# UTOS_V1_0.net
KiCad netlist of a schematic drawn in Altium Designer
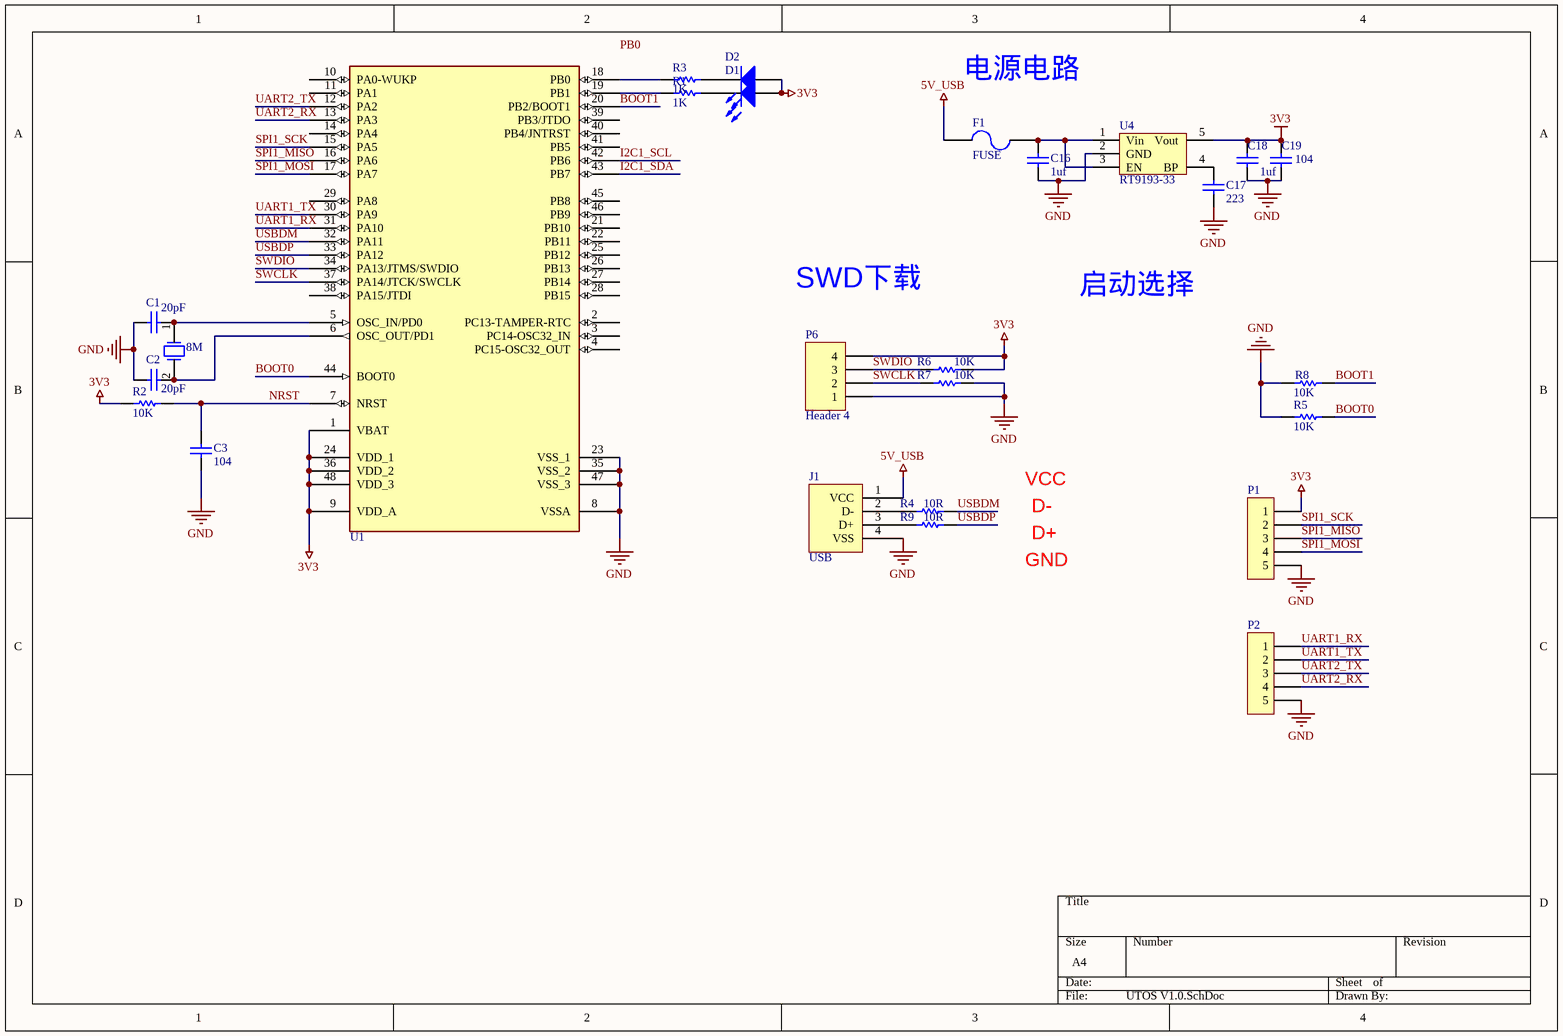
[diagram p0: UTOS V1.0.SchDoc]

(export (version "E")
  (design (tool "Eeschema 10.0.6"))
  (components
    (comp (ref "8M") (value "XTAL") (footprint "xtal") (libsource (lib "MYLIB") (part "XTAL")))
    (comp (ref "C1")
      (value "20pF")
      (footprint "C-RAD-0603")
      (description "Capacitor")
      (fields (field (name "Comment") "C0603") (field (name "PUBLISHER") "Altium Limited"))
      (libsource (lib "MYLIB") (part "C-RAD-0603"))
    )
    (comp (ref "C2")
      (value "20pF")
      (footprint "C-RAD-0603")
      (description "Capacitor")
      (fields (field (name "Comment") "C0603") (field (name "PUBLISHER") "Altium Limited"))
      (libsource (lib "MYLIB") (part "C-RAD-0603"))
    )
    (comp (ref "C3")
      (value "104")
      (footprint "C-RAD-0603")
      (description "Capacitor")
      (fields (field (name "Comment") "C0603") (field (name "PUBLISHER") "Altium Limited"))
      (libsource (lib "MYLIB") (part "C-RAD-0603"))
    )
    (comp (ref "C16")
      (value "1uf")
      (footprint "C-RAD-0603")
      (description "Capacitor")
      (libsource (lib "Cheetie Integrated Library 2017") (part "CAP"))
    )
    (comp (ref "C17")
      (value "223")
      (footprint "C-RAD-0603")
      (description "Capacitor")
      (libsource (lib "Cheetie Integrated Library 2017") (part "CAP"))
    )
    (comp (ref "C18")
      (value "1uf")
      (footprint "C-RAD-0603")
      (description "Capacitor")
      (libsource (lib "Cheetie Integrated Library 2017") (part "CAP"))
    )
    (comp (ref "C19")
      (value "104")
      (footprint "C-RAD-0603")
      (description "Capacitor")
      (libsource (lib "Cheetie Integrated Library 2017") (part "CAP"))
    )
    (comp (ref "D1")
      (value "D0603")
      (footprint "0603-1")
      (description "Typical RED, GREEN, YELLOW, AMBER GaAs LED")
      (fields (field (name "PUBLISHER") "Altium Limited"))
      (libsource (lib "MYLIB") (part "D0603"))
    )
    (comp (ref "D2")
      (value "D0603")
      (footprint "0603-1")
      (description "Typical RED, GREEN, YELLOW, AMBER GaAs LED")
      (fields (field (name "PUBLISHER") "Altium Limited"))
      (libsource (lib "MYLIB") (part "D0603"))
    )
    (comp (ref "F1") (value "FUSE") (footprint "0603-1") (libsource (lib "MYLIB") (part "FUSE")))
    (comp (ref "J1")
      (value "USB")
      (footprint "USB")
      (description "USB接口")
      (libsource (lib "Cheetie Integrated Library 2017") (part "USB"))
    )
    (comp (ref "P1")
      (value "~")
      (footprint "p5")
      (libsource (lib "Cheetie Integrated Library 2017") (part "p5"))
    )
    (comp (ref "P2")
      (value "~")
      (footprint "p5")
      (libsource (lib "Cheetie Integrated Library 2017") (part "p5"))
    )
    (comp (ref "P6")
      (value "Header 4")
      (footprint "p4")
      (description "Header, 4-Pin")
      (fields (field (name "PUBLISHER") "Altium Limited"))
      (libsource (lib "Miscellaneous Connectors") (part "Header 4"))
    )
    (comp (ref "R1")
      (value "1K")
      (footprint "0603-1")
      (description "Resistor")
      (fields (field (name "Comment") "R0603") (field (name "PUBLISHER") "Altium Limited"))
      (libsource (lib "MYLIB") (part "0603-1"))
    )
    (comp (ref "R2")
      (value "10K")
      (footprint "r0603")
      (description "Resistor")
      (fields (field (name "Comment") "R0603") (field (name "PUBLISHER") "Altium Limited"))
      (libsource (lib "MYLIB") (part "0603-1"))
    )
    (comp (ref "R3")
      (value "1K")
      (footprint "0603-1")
      (description "Resistor")
      (fields (field (name "Comment") "R0603") (field (name "PUBLISHER") "Altium Limited"))
      (libsource (lib "MYLIB") (part "0603-1"))
    )
    (comp (ref "R4")
      (value "10R")
      (footprint "0603-1")
      (description "Resistor")
      (fields (field (name "Comment") "R0805") (field (name "PUBLISHER") "Altium Limited"))
      (libsource (lib "component_lib") (part "R0805"))
    )
    (comp (ref "R5")
      (value "10K")
      (footprint "0603-1")
      (description "Resistor")
      (fields (field (name "Comment") "R0603") (field (name "PUBLISHER") "Altium Limited"))
      (libsource (lib "MYLIB") (part "0603-1"))
    )
    (comp (ref "R6")
      (value "10K")
      (footprint "0603-1")
      (description "Resistor")
      (fields (field (name "Comment") "R0805") (field (name "PUBLISHER") "Altium Limited"))
      (libsource (lib "component_lib") (part "R0805"))
    )
    (comp (ref "R7")
      (value "10K")
      (footprint "0603-1")
      (description "Resistor")
      (fields (field (name "Comment") "R0805") (field (name "PUBLISHER") "Altium Limited"))
      (libsource (lib "component_lib") (part "R0805"))
    )
    (comp (ref "R8")
      (value "10K")
      (footprint "0603-1")
      (description "Resistor")
      (fields (field (name "Comment") "R0603") (field (name "PUBLISHER") "Altium Limited"))
      (libsource (lib "MYLIB") (part "R0603"))
    )
    (comp (ref "R9")
      (value "10R")
      (footprint "0603-1")
      (description "Resistor")
      (fields (field (name "Comment") "R0805") (field (name "PUBLISHER") "Altium Limited"))
      (libsource (lib "component_lib") (part "R0805"))
    )
    (comp (ref "U1")
      (value "STM32F103C8T6")
      (footprint "LQFP48")
      (description "LowPower MCU")
      (libsource (lib "MYLIB") (part "STM32F103C8T6"))
    )
    (comp (ref "U4")
      (value "RT9193-33")
      (footprint "SOT23-5")
      (libsource (lib "Cheetie Integrated Library 2017") (part "RT9193-33"))
    )
  )
  (nets
    (net (code "1") (name "/BOOT0") (class "Default")
      (node (ref "R5") (pin "1") (pinfunction "1_1") (pintype "passive"))
      (node (ref "U1") (pin "44") (pinfunction "BOOT0_44") (pintype "input"))
    )
    (net (code "2") (name "/BOOT1") (class "Default")
      (node (ref "R8") (pin "2") (pinfunction "2_2") (pintype "passive"))
      (node (ref "U1") (pin "20") (pinfunction "PB2/BOOT1_20") (pintype "bidirectional"))
    )
    (net (code "3") (name "/I2C1_SCL") (class "Default")
      (node (ref "U1") (pin "42") (pinfunction "PB6_42") (pintype "bidirectional"))
    )
    (net (code "4") (name "/I2C1_SDA") (class "Default")
      (node (ref "U1") (pin "43") (pinfunction "PB7_43") (pintype "bidirectional"))
    )
    (net (code "5") (name "/NRST") (class "Default")
      (node (ref "C3") (pin "2") (pinfunction "2_2") (pintype "passive"))
      (node (ref "R2") (pin "1") (pinfunction "1_1") (pintype "passive"))
      (node (ref "U1") (pin "7") (pinfunction "NRST_7") (pintype "bidirectional"))
    )
    (net (code "7") (name "/SPI1_MISO") (class "Default")
      (node (ref "P1") (pin "3") (pinfunction "3_3") (pintype "passive"))
      (node (ref "U1") (pin "16") (pinfunction "PA6_16") (pintype "bidirectional"))
    )
    (net (code "8") (name "/SPI1_MOSI") (class "Default")
      (node (ref "P1") (pin "4") (pinfunction "4_4") (pintype "passive"))
      (node (ref "U1") (pin "17") (pinfunction "PA7_17") (pintype "bidirectional"))
    )
    (net (code "9") (name "/SPI1_SCK") (class "Default")
      (node (ref "P1") (pin "2") (pinfunction "2_2") (pintype "passive"))
      (node (ref "U1") (pin "15") (pinfunction "PA5_15") (pintype "bidirectional"))
    )
    (net (code "10") (name "/SWCLK") (class "Default")
      (node (ref "P6") (pin "2") (pinfunction "2_2") (pintype "passive"))
      (node (ref "R7") (pin "2") (pinfunction "2_2") (pintype "passive"))
      (node (ref "U1") (pin "37") (pinfunction "PA14/JTCK/SWCLK_37") (pintype "bidirectional"))
    )
    (net (code "11") (name "/SWDIO") (class "Default")
      (node (ref "P6") (pin "3") (pinfunction "3_3") (pintype "passive"))
      (node (ref "R6") (pin "2") (pinfunction "2_2") (pintype "passive"))
      (node (ref "U1") (pin "34") (pinfunction "PA13/JTMS/SWDIO_34") (pintype "bidirectional"))
    )
    (net (code "12") (name "/UART1_RX") (class "Default")
      (node (ref "P2") (pin "1") (pinfunction "1_1") (pintype "passive"))
      (node (ref "U1") (pin "31") (pinfunction "PA10_31") (pintype "bidirectional"))
    )
    (net (code "13") (name "/UART1_TX") (class "Default")
      (node (ref "P2") (pin "2") (pinfunction "2_2") (pintype "passive"))
      (node (ref "U1") (pin "30") (pinfunction "PA9_30") (pintype "bidirectional"))
    )
    (net (code "14") (name "/UART2_RX") (class "Default")
      (node (ref "P2") (pin "4") (pinfunction "4_4") (pintype "passive"))
      (node (ref "U1") (pin "13") (pinfunction "PA3_13") (pintype "bidirectional"))
    )
    (net (code "15") (name "/UART2_TX") (class "Default")
      (node (ref "P2") (pin "3") (pinfunction "3_3") (pintype "passive"))
      (node (ref "U1") (pin "12") (pinfunction "PA2_12") (pintype "bidirectional"))
    )
    (net (code "16") (name "/USBDM") (class "Default")
      (node (ref "R4") (pin "1") (pinfunction "1_1") (pintype "passive"))
      (node (ref "U1") (pin "32") (pinfunction "PA11_32") (pintype "bidirectional"))
    )
    (net (code "17") (name "/USBDP") (class "Default")
      (node (ref "R9") (pin "1") (pinfunction "1_1") (pintype "passive"))
      (node (ref "U1") (pin "33") (pinfunction "PA12_33") (pintype "bidirectional"))
    )
    (net (code "18") (name "3V3") (class "Default")
      (node (ref "C18") (pin "2") (pinfunction "2_2") (pintype "passive"))
      (node (ref "C19") (pin "2") (pinfunction "2_2") (pintype "passive"))
      (node (ref "D1") (pin "1") (pinfunction "A_1") (pintype "passive"))
      (node (ref "D2") (pin "1") (pinfunction "A_1") (pintype "passive"))
      (node (ref "P1") (pin "1") (pinfunction "1_1") (pintype "passive"))
      (node (ref "P6") (pin "4") (pinfunction "4_4") (pintype "passive"))
      (node (ref "R2") (pin "2") (pinfunction "2_2") (pintype "passive"))
      (node (ref "R6") (pin "1") (pinfunction "1_1") (pintype "passive"))
      (node (ref "U1") (pin "1") (pinfunction "VBAT_1") (pintype "passive"))
      (node (ref "U1") (pin "24") (pinfunction "VDD_1_24") (pintype "passive"))
      (node (ref "U1") (pin "36") (pinfunction "VDD_2_36") (pintype "passive"))
      (node (ref "U1") (pin "48") (pinfunction "VDD_3_48") (pintype "passive"))
      (node (ref "U1") (pin "9") (pinfunction "VDD_A_9") (pintype "passive"))
      (node (ref "U4") (pin "5") (pinfunction "Vout_5") (pintype "passive"))
    )
    (net (code "19") (name "5V_USB") (class "Default")
      (node (ref "F1") (pin "2") (pinfunction "2_2") (pintype "passive"))
      (node (ref "J1") (pin "1") (pinfunction "VCC_1") (pintype "passive"))
    )
    (net (code "20") (name "GND") (class "Default")
      (node (ref "C1") (pin "2") (pinfunction "2_2") (pintype "passive"))
      (node (ref "C16") (pin "1") (pinfunction "1_1") (pintype "passive"))
      (node (ref "C17") (pin "1") (pinfunction "1_1") (pintype "passive"))
      (node (ref "C18") (pin "1") (pinfunction "1_1") (pintype "passive"))
      (node (ref "C19") (pin "1") (pinfunction "1_1") (pintype "passive"))
      (node (ref "C2") (pin "2") (pinfunction "2_2") (pintype "passive"))
      (node (ref "C3") (pin "1") (pinfunction "1_1") (pintype "passive"))
      (node (ref "J1") (pin "4") (pinfunction "VSS_4") (pintype "passive"))
      (node (ref "P1") (pin "5") (pinfunction "5_5") (pintype "passive"))
      (node (ref "P2") (pin "5") (pinfunction "5_5") (pintype "passive"))
      (node (ref "P6") (pin "1") (pinfunction "1_1") (pintype "passive"))
      (node (ref "R5") (pin "2") (pinfunction "2_2") (pintype "passive"))
      (node (ref "R7") (pin "1") (pinfunction "1_1") (pintype "passive"))
      (node (ref "R8") (pin "1") (pinfunction "1_1") (pintype "passive"))
      (node (ref "U1") (pin "23") (pinfunction "VSS_1_23") (pintype "passive"))
      (node (ref "U1") (pin "35") (pinfunction "VSS_2_35") (pintype "passive"))
      (node (ref "U1") (pin "47") (pinfunction "VSS_3_47") (pintype "passive"))
      (node (ref "U1") (pin "8") (pinfunction "VSSA_8") (pintype "passive"))
      (node (ref "U4") (pin "2") (pinfunction "GND_2") (pintype "passive"))
    )
    (net (code "21") (name "Net-(D1-K)") (class "Default")
      (node (ref "D1") (pin "2") (pinfunction "K_2") (pintype "passive"))
      (node (ref "R1") (pin "2") (pinfunction "2_2") (pintype "passive"))
    )
    (net (code "22") (name "Net-(D2-K)") (class "Default")
      (node (ref "D2") (pin "2") (pinfunction "K_2") (pintype "passive"))
      (node (ref "R3") (pin "2") (pinfunction "2_2") (pintype "passive"))
    )
    (net (code "23") (name "Net-(J1-D+)") (class "Default")
      (node (ref "J1") (pin "3") (pinfunction "D+_3") (pintype "passive"))
      (node (ref "R9") (pin "2") (pinfunction "2_2") (pintype "passive"))
    )
    (net (code "24") (name "Net-(J1-D-)") (class "Default")
      (node (ref "J1") (pin "2") (pinfunction "D-_2") (pintype "passive"))
      (node (ref "R4") (pin "2") (pinfunction "2_2") (pintype "passive"))
    )
    (net (code "25") (name "Net-(U1-OSC_IN{slash}PD0)") (class "Default")
      (node (ref "8M") (pin "1") (pinfunction "1_1") (pintype "passive"))
      (node (ref "C1") (pin "1") (pinfunction "1_1") (pintype "passive"))
      (node (ref "U1") (pin "5") (pinfunction "OSC_IN/PD0_5") (pintype "input"))
    )
    (net (code "26") (name "Net-(U1-OSC_OUT{slash}PD1)") (class "Default")
      (node (ref "8M") (pin "2") (pinfunction "2_2") (pintype "passive"))
      (node (ref "C2") (pin "1") (pinfunction "1_1") (pintype "passive"))
      (node (ref "U1") (pin "6") (pinfunction "OSC_OUT/PD1_6") (pintype "output"))
    )
    (net (code "27") (name "Net-(U1-PB0)") (class "Default")
      (node (ref "R3") (pin "1") (pinfunction "1_1") (pintype "passive"))
      (node (ref "U1") (pin "18") (pinfunction "PB0_18") (pintype "bidirectional"))
    )
    (net (code "28") (name "Net-(U1-PB1)") (class "Default")
      (node (ref "R1") (pin "1") (pinfunction "1_1") (pintype "passive"))
      (node (ref "U1") (pin "19") (pinfunction "PB1_19") (pintype "bidirectional"))
    )
    (net (code "29") (name "Net-(U4-BP)") (class "Default")
      (node (ref "C17") (pin "2") (pinfunction "2_2") (pintype "passive"))
      (node (ref "U4") (pin "4") (pinfunction "BP_4") (pintype "passive"))
    )
    (net (code "30") (name "Net-(U4-EN)") (class "Default")
      (node (ref "C16") (pin "2") (pinfunction "2_2") (pintype "passive"))
      (node (ref "F1") (pin "1") (pinfunction "1_1") (pintype "passive"))
      (node (ref "U4") (pin "1") (pinfunction "Vin_1") (pintype "passive"))
      (node (ref "U4") (pin "3") (pinfunction "EN_3") (pintype "passive"))
    )
    (net (code "31") (name "unconnected-(U1-PA0-WUKP-Pad10)") (class "Default")
      (node (ref "U1") (pin "10") (pinfunction "PA0-WUKP_10") (pintype "bidirectional"))
    )
    (net (code "32") (name "unconnected-(U1-PA1-Pad11)") (class "Default")
      (node (ref "U1") (pin "11") (pinfunction "PA1_11") (pintype "bidirectional"))
    )
    (net (code "33") (name "unconnected-(U1-PA4-Pad14)") (class "Default")
      (node (ref "U1") (pin "14") (pinfunction "PA4_14") (pintype "bidirectional"))
    )
    (net (code "34") (name "unconnected-(U1-PA8-Pad29)") (class "Default")
      (node (ref "U1") (pin "29") (pinfunction "PA8_29") (pintype "bidirectional"))
    )
    (net (code "35") (name "unconnected-(U1-PA15{slash}JTDI-Pad38)") (class "Default")
      (node (ref "U1") (pin "38") (pinfunction "PA15/JTDI_38") (pintype "bidirectional"))
    )
    (net (code "36") (name "unconnected-(U1-PB3{slash}JTDO-Pad39)") (class "Default")
      (node (ref "U1") (pin "39") (pinfunction "PB3/JTDO_39") (pintype "bidirectional"))
    )
    (net (code "37") (name "unconnected-(U1-PB4{slash}JNTRST-Pad40)") (class "Default")
      (node (ref "U1") (pin "40") (pinfunction "PB4/JNTRST_40") (pintype "bidirectional"))
    )
    (net (code "38") (name "unconnected-(U1-PB5-Pad41)") (class "Default")
      (node (ref "U1") (pin "41") (pinfunction "PB5_41") (pintype "bidirectional"))
    )
    (net (code "39") (name "unconnected-(U1-PB8-Pad45)") (class "Default")
      (node (ref "U1") (pin "45") (pinfunction "PB8_45") (pintype "bidirectional"))
    )
    (net (code "40") (name "unconnected-(U1-PB9-Pad46)") (class "Default")
      (node (ref "U1") (pin "46") (pinfunction "PB9_46") (pintype "bidirectional"))
    )
    (net (code "41") (name "unconnected-(U1-PB10-Pad21)") (class "Default")
      (node (ref "U1") (pin "21") (pinfunction "PB10_21") (pintype "bidirectional"))
    )
    (net (code "42") (name "unconnected-(U1-PB11-Pad22)") (class "Default")
      (node (ref "U1") (pin "22") (pinfunction "PB11_22") (pintype "bidirectional"))
    )
    (net (code "43") (name "unconnected-(U1-PB12-Pad25)") (class "Default")
      (node (ref "U1") (pin "25") (pinfunction "PB12_25") (pintype "bidirectional"))
    )
    (net (code "44") (name "unconnected-(U1-PB13-Pad26)") (class "Default")
      (node (ref "U1") (pin "26") (pinfunction "PB13_26") (pintype "bidirectional"))
    )
    (net (code "45") (name "unconnected-(U1-PB14-Pad27)") (class "Default")
      (node (ref "U1") (pin "27") (pinfunction "PB14_27") (pintype "bidirectional"))
    )
    (net (code "46") (name "unconnected-(U1-PB15-Pad28)") (class "Default")
      (node (ref "U1") (pin "28") (pinfunction "PB15_28") (pintype "bidirectional"))
    )
    (net (code "47") (name "unconnected-(U1-PC13-TAMPER-RTC-Pad2)") (class "Default")
      (node (ref "U1") (pin "2") (pinfunction "PC13-TAMPER-RTC_2") (pintype "bidirectional"))
    )
    (net (code "48") (name "unconnected-(U1-PC14-OSC32_IN-Pad3)") (class "Default")
      (node (ref "U1") (pin "3") (pinfunction "PC14-OSC32_IN_3") (pintype "bidirectional"))
    )
    (net (code "49") (name "unconnected-(U1-PC15-OSC32_OUT-Pad4)") (class "Default")
      (node (ref "U1") (pin "4") (pinfunction "PC15-OSC32_OUT_4") (pintype "bidirectional"))
    )
  )
)
